# BoardSchematics.net
KiCad netlist of a schematic drawn in EAGLE
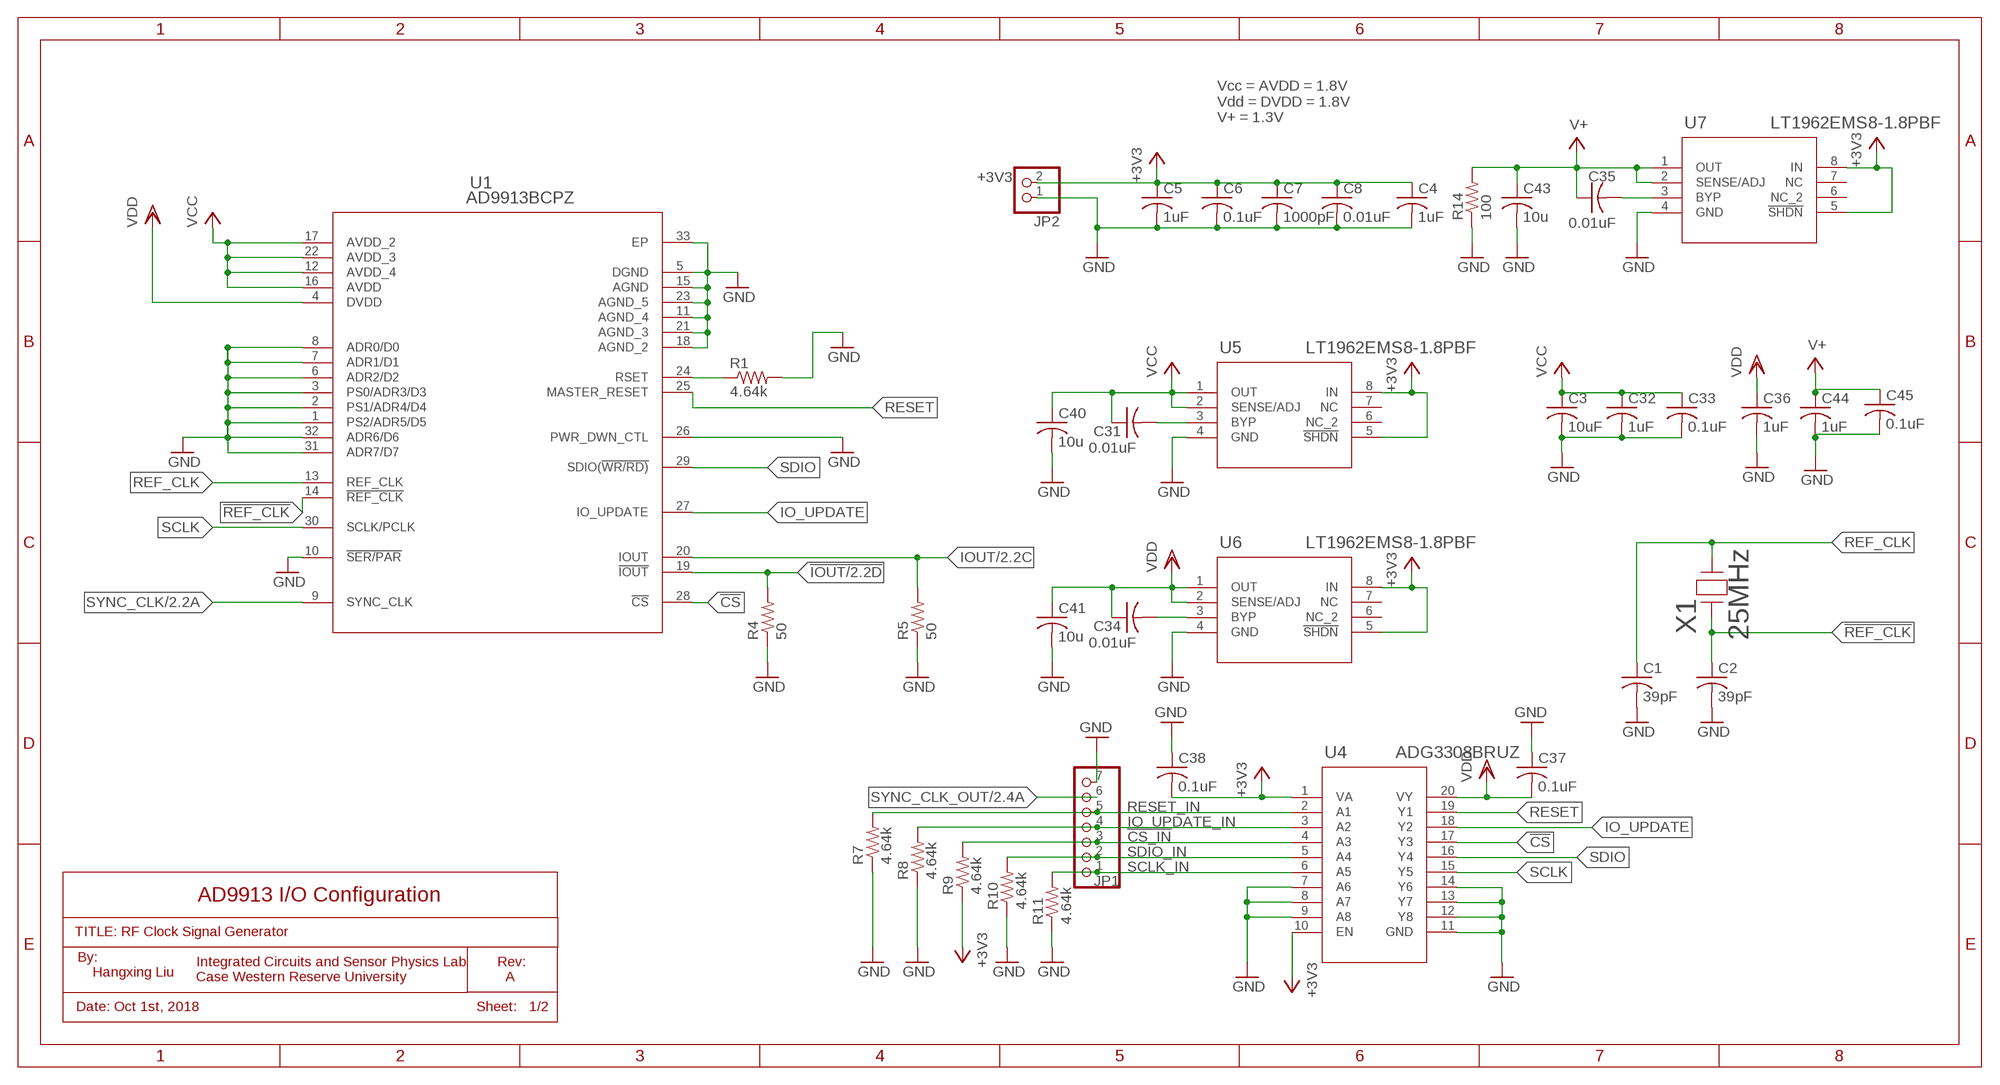
[diagram p0: schematic, sheet 1]
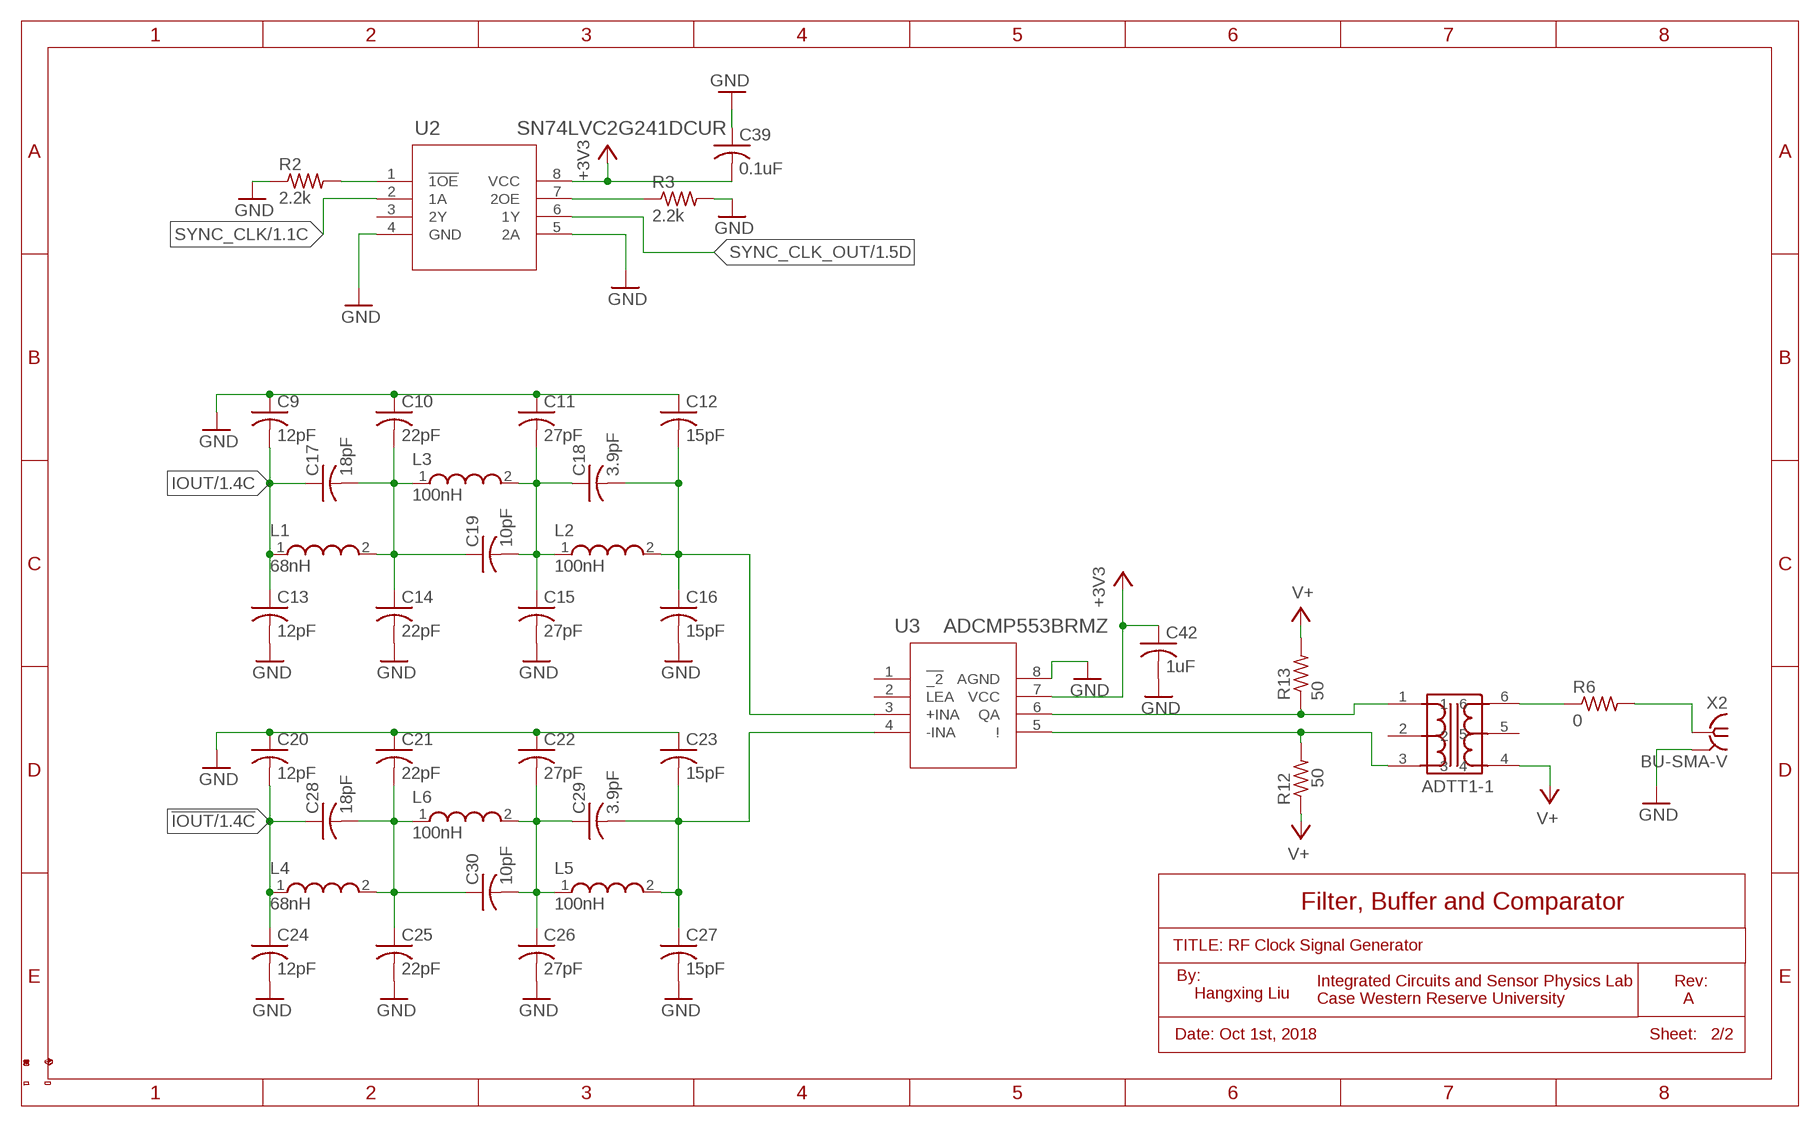
[diagram p1: schematic, sheet 2]

(export (version "E")
  (design (tool "Eeschema 10.0.6"))
  (components
    (comp (ref "ATT1-1")
      (value "PWB-1-CLCD542")
      (footprint "eagle-import:CD542")
      (libsource (lib "eagle-import") (part "PWB-1-CLCD542"))
    )
    (comp (ref "C9")
      (value "12pF")
      (footprint "eagle-import:C0603K")
      (libsource (lib "eagle-import") (part "C-USC0603K"))
    )
    (comp (ref "C10")
      (value "22pF")
      (footprint "eagle-import:C0603K")
      (libsource (lib "eagle-import") (part "C-USC0603K"))
    )
    (comp (ref "C11")
      (value "27pF")
      (footprint "eagle-import:C0603K")
      (libsource (lib "eagle-import") (part "C-USC0603K"))
    )
    (comp (ref "C12")
      (value "15pF")
      (footprint "eagle-import:C0603K")
      (libsource (lib "eagle-import") (part "C-USC0603K"))
    )
    (comp (ref "C13")
      (value "12pF")
      (footprint "eagle-import:C0603K")
      (libsource (lib "eagle-import") (part "C-USC0603K"))
    )
    (comp (ref "C14")
      (value "22pF")
      (footprint "eagle-import:C0603K")
      (libsource (lib "eagle-import") (part "C-USC0603K"))
    )
    (comp (ref "C15")
      (value "27pF")
      (footprint "eagle-import:C0603K")
      (libsource (lib "eagle-import") (part "C-USC0603K"))
    )
    (comp (ref "C16")
      (value "15pF")
      (footprint "eagle-import:C0603K")
      (libsource (lib "eagle-import") (part "C-USC0603K"))
    )
    (comp (ref "C17")
      (value "18pF")
      (footprint "eagle-import:C0603K")
      (libsource (lib "eagle-import") (part "C-USC0603K"))
    )
    (comp (ref "C18")
      (value "3.9pF")
      (footprint "eagle-import:C0603K")
      (libsource (lib "eagle-import") (part "C-USC0603K"))
    )
    (comp (ref "C19")
      (value "10pF")
      (footprint "eagle-import:C0603K")
      (libsource (lib "eagle-import") (part "C-USC0603K"))
    )
    (comp (ref "C20")
      (value "12pF")
      (footprint "eagle-import:C0603K")
      (libsource (lib "eagle-import") (part "C-USC0603K"))
    )
    (comp (ref "C21")
      (value "22pF")
      (footprint "eagle-import:C0603K")
      (libsource (lib "eagle-import") (part "C-USC0603K"))
    )
    (comp (ref "C22")
      (value "27pF")
      (footprint "eagle-import:C0603K")
      (libsource (lib "eagle-import") (part "C-USC0603K"))
    )
    (comp (ref "C23")
      (value "15pF")
      (footprint "eagle-import:C0603K")
      (libsource (lib "eagle-import") (part "C-USC0603K"))
    )
    (comp (ref "C24")
      (value "12pF")
      (footprint "eagle-import:C0603K")
      (libsource (lib "eagle-import") (part "C-USC0603K"))
    )
    (comp (ref "C25")
      (value "22pF")
      (footprint "eagle-import:C0603K")
      (libsource (lib "eagle-import") (part "C-USC0603K"))
    )
    (comp (ref "C26")
      (value "27pF")
      (footprint "eagle-import:C0603K")
      (libsource (lib "eagle-import") (part "C-USC0603K"))
    )
    (comp (ref "C27")
      (value "15pF")
      (footprint "eagle-import:C0603K")
      (libsource (lib "eagle-import") (part "C-USC0603K"))
    )
    (comp (ref "C28")
      (value "18pF")
      (footprint "eagle-import:C0603K")
      (libsource (lib "eagle-import") (part "C-USC0603K"))
    )
    (comp (ref "C29")
      (value "3.9pF")
      (footprint "eagle-import:C0603K")
      (libsource (lib "eagle-import") (part "C-USC0603K"))
    )
    (comp (ref "C30")
      (value "10pF")
      (footprint "eagle-import:C0603K")
      (libsource (lib "eagle-import") (part "C-USC0603K"))
    )
    (comp (ref "C39")
      (value "0.1uF")
      (footprint "eagle-import:C0603K")
      (libsource (lib "eagle-import") (part "C-USC0603K"))
    )
    (comp (ref "C42")
      (value "1uF")
      (footprint "eagle-import:C0603K")
      (libsource (lib "eagle-import") (part "C-USC0603K"))
    )
    (comp (ref "L1")
      (value "68nH")
      (footprint "eagle-import:WE-PMI_1008")
      (libsource (lib "eagle-import") (part "WE-PMI_1008"))
    )
    (comp (ref "L2")
      (value "100nH")
      (footprint "eagle-import:WE-PMI_1008")
      (libsource (lib "eagle-import") (part "WE-PMI_1008"))
    )
    (comp (ref "L3")
      (value "100nH")
      (footprint "eagle-import:WE-PMI_1008")
      (libsource (lib "eagle-import") (part "WE-PMI_1008"))
    )
    (comp (ref "L4")
      (value "68nH")
      (footprint "eagle-import:WE-PMI_1008")
      (libsource (lib "eagle-import") (part "WE-PMI_1008"))
    )
    (comp (ref "L5")
      (value "100nH")
      (footprint "eagle-import:WE-PMI_1008")
      (libsource (lib "eagle-import") (part "WE-PMI_1008"))
    )
    (comp (ref "L6")
      (value "100nH")
      (footprint "eagle-import:WE-PMI_1008")
      (libsource (lib "eagle-import") (part "WE-PMI_1008"))
    )
    (comp (ref "R2")
      (value "2.2k")
      (footprint "eagle-import:R0603")
      (libsource (lib "eagle-import") (part "R-US_R0603"))
    )
    (comp (ref "R3")
      (value "2.2k")
      (footprint "eagle-import:R0603")
      (libsource (lib "eagle-import") (part "R-US_R0603"))
    )
    (comp (ref "R6")
      (value "0")
      (footprint "eagle-import:R0603")
      (libsource (lib "eagle-import") (part "R-US_R0603"))
    )
    (comp (ref "R12")
      (value "50")
      (footprint "eagle-import:R0603")
      (libsource (lib "eagle-import") (part "R-US_R0603"))
    )
    (comp (ref "R13")
      (value "50")
      (footprint "eagle-import:R0603")
      (libsource (lib "eagle-import") (part "R-US_R0603"))
    )
    (comp (ref "U2")
      (value "SN74LVC2G241DCUR")
      (footprint "eagle-import:DCU8")
      (libsource (lib "eagle-import") (part "SN74LVC2G241DCUR"))
    )
    (comp (ref "U3")
      (value "ADCMP553BRMZ")
      (footprint "eagle-import:RM_8")
      (libsource (lib "eagle-import") (part "ADCMP553BRMZ"))
    )
    (comp (ref "X2")
      (value "BU-SMA-V")
      (footprint "eagle-import:BU-SMA-V")
      (libsource (lib "eagle-import") (part "BU-SMA-V"))
    )
    (comp (ref "C1")
      (value "39pF")
      (footprint "eagle-import:C1608")
      (libsource (lib "eagle-import") (part "C-USC1608"))
    )
    (comp (ref "C2")
      (value "39pF")
      (footprint "eagle-import:C1608")
      (libsource (lib "eagle-import") (part "C-USC1608"))
    )
    (comp (ref "C3")
      (value "10uF")
      (footprint "eagle-import:C0603K")
      (libsource (lib "eagle-import") (part "C-USC0603K"))
    )
    (comp (ref "C4")
      (value "1uF")
      (footprint "eagle-import:C0603K")
      (libsource (lib "eagle-import") (part "C-USC0603K"))
    )
    (comp (ref "C5")
      (value "1uF")
      (footprint "eagle-import:C0603K")
      (libsource (lib "eagle-import") (part "C-USC0603K"))
    )
    (comp (ref "C6")
      (value "0.1uF")
      (footprint "eagle-import:C0603K")
      (libsource (lib "eagle-import") (part "C-USC0603K"))
    )
    (comp (ref "C7")
      (value "1000pF")
      (footprint "eagle-import:C0603K")
      (libsource (lib "eagle-import") (part "C-USC0603K"))
    )
    (comp (ref "C8")
      (value "0.01uF")
      (footprint "eagle-import:C0603K")
      (libsource (lib "eagle-import") (part "C-USC0603K"))
    )
    (comp (ref "C31")
      (value "0.01uF")
      (footprint "eagle-import:C0603K")
      (libsource (lib "eagle-import") (part "C-USC0603K"))
    )
    (comp (ref "C32")
      (value "1uF")
      (footprint "eagle-import:C0603K")
      (libsource (lib "eagle-import") (part "C-USC0603K"))
    )
    (comp (ref "C33")
      (value "0.1uF")
      (footprint "eagle-import:C0603K")
      (libsource (lib "eagle-import") (part "C-USC0603K"))
    )
    (comp (ref "C34")
      (value "0.01uF")
      (footprint "eagle-import:C0603K")
      (libsource (lib "eagle-import") (part "C-USC0603K"))
    )
    (comp (ref "C35")
      (value "0.01uF")
      (footprint "eagle-import:C0603K")
      (libsource (lib "eagle-import") (part "C-USC0603K"))
    )
    (comp (ref "C36")
      (value "1uF")
      (footprint "eagle-import:C0603K")
      (libsource (lib "eagle-import") (part "C-USC0603K"))
    )
    (comp (ref "C37")
      (value "0.1uF")
      (footprint "eagle-import:C0603K")
      (libsource (lib "eagle-import") (part "C-USC0603K"))
    )
    (comp (ref "C38")
      (value "0.1uF")
      (footprint "eagle-import:C0603K")
      (libsource (lib "eagle-import") (part "C-USC0603K"))
    )
    (comp (ref "C40")
      (value "10u")
      (footprint "eagle-import:C0603K")
      (libsource (lib "eagle-import") (part "C-USC0603K"))
    )
    (comp (ref "C41")
      (value "10u")
      (footprint "eagle-import:C0603K")
      (libsource (lib "eagle-import") (part "C-USC0603K"))
    )
    (comp (ref "C43")
      (value "10u")
      (footprint "eagle-import:C0603K")
      (libsource (lib "eagle-import") (part "C-USC0603K"))
    )
    (comp (ref "C44")
      (value "1uF")
      (footprint "eagle-import:C0603K")
      (libsource (lib "eagle-import") (part "C-USC0603K"))
    )
    (comp (ref "C45")
      (value "0.1uF")
      (footprint "eagle-import:C0603K")
      (libsource (lib "eagle-import") (part "C-USC0603K"))
    )
    (comp (ref "JP1")
      (value "PINHD-1X7")
      (footprint "eagle-import:1X07")
      (libsource (lib "eagle-import") (part "PINHD-1X7"))
    )
    (comp (ref "JP2")
      (value "PINHD-1X2")
      (footprint "eagle-import:1X02")
      (libsource (lib "eagle-import") (part "PINHD-1X2"))
    )
    (comp (ref "R1")
      (value "4.64k")
      (footprint "eagle-import:R0603")
      (libsource (lib "eagle-import") (part "R-US_R0603"))
    )
    (comp (ref "R4")
      (value "50")
      (footprint "eagle-import:R0603")
      (libsource (lib "eagle-import") (part "R-US_R0603"))
    )
    (comp (ref "R5")
      (value "50")
      (footprint "eagle-import:R0603")
      (libsource (lib "eagle-import") (part "R-US_R0603"))
    )
    (comp (ref "R7")
      (value "4.64k")
      (footprint "eagle-import:R0603")
      (libsource (lib "eagle-import") (part "R-US_R0603"))
    )
    (comp (ref "R8")
      (value "4.64k")
      (footprint "eagle-import:R0603")
      (libsource (lib "eagle-import") (part "R-US_R0603"))
    )
    (comp (ref "R9")
      (value "4.64k")
      (footprint "eagle-import:R0603")
      (libsource (lib "eagle-import") (part "R-US_R0603"))
    )
    (comp (ref "R10")
      (value "4.64k")
      (footprint "eagle-import:R0603")
      (libsource (lib "eagle-import") (part "R-US_R0603"))
    )
    (comp (ref "R11")
      (value "4.64k")
      (footprint "eagle-import:R0603")
      (libsource (lib "eagle-import") (part "R-US_R0603"))
    )
    (comp (ref "R14")
      (value "100")
      (footprint "eagle-import:R0603")
      (libsource (lib "eagle-import") (part "R-US_R0603"))
    )
    (comp (ref "U1")
      (value "AD9913BCPZ")
      (footprint "eagle-import:CP_32_2")
      (libsource (lib "eagle-import") (part "AD9913BCPZ"))
    )
    (comp (ref "U4")
      (value "ADG3308BRUZ")
      (footprint "eagle-import:RU_20")
      (libsource (lib "eagle-import") (part "ADG3308BRUZ"))
    )
    (comp (ref "U5")
      (value "LT1962EMS8-1.8PBF")
      (footprint "eagle-import:MSOP-8_MS")
      (fields (field (name "MANUFACTURER_PART_NUMBER") "LT1962EMS81.8#PBF"))
      (libsource (lib "eagle-import") (part "LT1962EMS8-1.8PBF"))
    )
    (comp (ref "U6")
      (value "LT1962EMS8-1.8PBF")
      (footprint "eagle-import:MSOP-8_MS")
      (fields (field (name "MANUFACTURER_PART_NUMBER") "LT1962EMS81.8#PBF"))
      (libsource (lib "eagle-import") (part "LT1962EMS8-1.8PBF"))
    )
    (comp (ref "U7")
      (value "LT1962EMS8-1.8PBF")
      (footprint "eagle-import:MSOP-8_MS")
      (fields (field (name "MANUFACTURER_PART_NUMBER") "LT1962EMS81.8#PBF"))
      (libsource (lib "eagle-import") (part "LT1962EMS8-1.8PBF"))
    )
    (comp (ref "X1")
      (value "25MHz")
      (footprint "eagle-import:CRYSTAL_HC49SDLF")
      (fields (field (name "MANUFACTURER_PART_NUMBER") "FOXSDLF250F20"))
      (libsource (lib "eagle-import") (part "FOXSDLF/250F-20"))
    )
  )
  (nets
    (net (code "1") (name "+3V3") (class "Default")
      (node (ref "C38") (pin "2") (pinfunction "2_2") (pintype "passive"))
      (node (ref "C39") (pin "2") (pinfunction "2_2") (pintype "passive"))
      (node (ref "C4") (pin "1") (pinfunction "1_1") (pintype "passive"))
      (node (ref "C42") (pin "1") (pinfunction "1_1") (pintype "passive"))
      (node (ref "C5") (pin "1") (pinfunction "1_1") (pintype "passive"))
      (node (ref "C6") (pin "1") (pinfunction "1_1") (pintype "passive"))
      (node (ref "C7") (pin "1") (pinfunction "1_1") (pintype "passive"))
      (node (ref "C8") (pin "1") (pinfunction "1_1") (pintype "passive"))
      (node (ref "JP2") (pin "2") (pinfunction "2_2") (pintype "passive"))
      (node (ref "R9") (pin "1") (pinfunction "1_1") (pintype "passive"))
      (node (ref "U2") (pin "8") (pinfunction "VCC_8") (pintype "power_in"))
      (node (ref "U3") (pin "7") (pinfunction "VCC_7") (pintype "power_in"))
      (node (ref "U4") (pin "1") (pinfunction "VA_1") (pintype "power_in"))
      (node (ref "U4") (pin "10") (pinfunction "EN_10") (pintype "passive"))
      (node (ref "U5") (pin "5") (pinfunction "~{SHDN}_5") (pintype "output"))
      (node (ref "U5") (pin "8") (pinfunction "IN_8") (pintype "input"))
      (node (ref "U6") (pin "5") (pinfunction "~{SHDN}_5") (pintype "output"))
      (node (ref "U6") (pin "8") (pinfunction "IN_8") (pintype "input"))
      (node (ref "U7") (pin "5") (pinfunction "~{SHDN}_5") (pintype "output"))
      (node (ref "U7") (pin "8") (pinfunction "IN_8") (pintype "input"))
    )
    (net (code "2") (name "GND") (class "Default")
      (node (ref "C1") (pin "2") (pinfunction "2_2") (pintype "passive"))
      (node (ref "C10") (pin "1") (pinfunction "1_1") (pintype "passive"))
      (node (ref "C11") (pin "1") (pinfunction "1_1") (pintype "passive"))
      (node (ref "C12") (pin "1") (pinfunction "1_1") (pintype "passive"))
      (node (ref "C13") (pin "2") (pinfunction "2_2") (pintype "passive"))
      (node (ref "C14") (pin "2") (pinfunction "2_2") (pintype "passive"))
      (node (ref "C15") (pin "2") (pinfunction "2_2") (pintype "passive"))
      (node (ref "C16") (pin "2") (pinfunction "2_2") (pintype "passive"))
      (node (ref "C2") (pin "2") (pinfunction "2_2") (pintype "passive"))
      (node (ref "C20") (pin "1") (pinfunction "1_1") (pintype "passive"))
      (node (ref "C21") (pin "1") (pinfunction "1_1") (pintype "passive"))
      (node (ref "C22") (pin "1") (pinfunction "1_1") (pintype "passive"))
      (node (ref "C23") (pin "1") (pinfunction "1_1") (pintype "passive"))
      (node (ref "C24") (pin "2") (pinfunction "2_2") (pintype "passive"))
      (node (ref "C25") (pin "2") (pinfunction "2_2") (pintype "passive"))
      (node (ref "C26") (pin "2") (pinfunction "2_2") (pintype "passive"))
      (node (ref "C27") (pin "2") (pinfunction "2_2") (pintype "passive"))
      (node (ref "C3") (pin "2") (pinfunction "2_2") (pintype "passive"))
      (node (ref "C32") (pin "2") (pinfunction "2_2") (pintype "passive"))
      (node (ref "C33") (pin "2") (pinfunction "2_2") (pintype "passive"))
      (node (ref "C36") (pin "2") (pinfunction "2_2") (pintype "passive"))
      (node (ref "C37") (pin "1") (pinfunction "1_1") (pintype "passive"))
      (node (ref "C38") (pin "1") (pinfunction "1_1") (pintype "passive"))
      (node (ref "C39") (pin "1") (pinfunction "1_1") (pintype "passive"))
      (node (ref "C4") (pin "2") (pinfunction "2_2") (pintype "passive"))
      (node (ref "C40") (pin "2") (pinfunction "2_2") (pintype "passive"))
      (node (ref "C41") (pin "2") (pinfunction "2_2") (pintype "passive"))
      (node (ref "C42") (pin "2") (pinfunction "2_2") (pintype "passive"))
      (node (ref "C43") (pin "2") (pinfunction "2_2") (pintype "passive"))
      (node (ref "C44") (pin "2") (pinfunction "2_2") (pintype "passive"))
      (node (ref "C45") (pin "2") (pinfunction "2_2") (pintype "passive"))
      (node (ref "C5") (pin "2") (pinfunction "2_2") (pintype "passive"))
      (node (ref "C6") (pin "2") (pinfunction "2_2") (pintype "passive"))
      (node (ref "C7") (pin "2") (pinfunction "2_2") (pintype "passive"))
      (node (ref "C8") (pin "2") (pinfunction "2_2") (pintype "passive"))
      (node (ref "C9") (pin "1") (pinfunction "1_1") (pintype "passive"))
      (node (ref "JP1") (pin "7") (pinfunction "7_7") (pintype "passive"))
      (node (ref "JP2") (pin "1") (pinfunction "1_1") (pintype "passive"))
      (node (ref "R1") (pin "2") (pinfunction "2_2") (pintype "passive"))
      (node (ref "R10") (pin "1") (pinfunction "1_1") (pintype "passive"))
      (node (ref "R11") (pin "1") (pinfunction "1_1") (pintype "passive"))
      (node (ref "R14") (pin "1") (pinfunction "1_1") (pintype "passive"))
      (node (ref "R2") (pin "1") (pinfunction "1_1") (pintype "passive"))
      (node (ref "R3") (pin "2") (pinfunction "2_2") (pintype "passive"))
      (node (ref "R4") (pin "1") (pinfunction "1_1") (pintype "passive"))
      (node (ref "R5") (pin "1") (pinfunction "1_1") (pintype "passive"))
      (node (ref "R7") (pin "1") (pinfunction "1_1") (pintype "passive"))
      (node (ref "R8") (pin "1") (pinfunction "1_1") (pintype "passive"))
      (node (ref "U1") (pin "1") (pinfunction "PS2/ADR5/D5_1") (pintype "passive"))
      (node (ref "U1") (pin "10") (pinfunction "~{SER/PAR}_10") (pintype "passive"))
      (node (ref "U1") (pin "11") (pinfunction "AGND_4_11") (pintype "passive"))
      (node (ref "U1") (pin "15") (pinfunction "AGND_15") (pintype "passive"))
      (node (ref "U1") (pin "18") (pinfunction "AGND_2_18") (pintype "passive"))
      (node (ref "U1") (pin "2") (pinfunction "PS1/ADR4/D4_2") (pintype "passive"))
      (node (ref "U1") (pin "21") (pinfunction "AGND_3_21") (pintype "passive"))
      (node (ref "U1") (pin "23") (pinfunction "AGND_5_23") (pintype "passive"))
      (node (ref "U1") (pin "26") (pinfunction "PWR_DWN_CTL_26") (pintype "passive"))
      (node (ref "U1") (pin "3") (pinfunction "PS0/ADR3/D3_3") (pintype "passive"))
      (node (ref "U1") (pin "31") (pinfunction "ADR7/D7_31") (pintype "passive"))
      (node (ref "U1") (pin "32") (pinfunction "ADR6/D6_32") (pintype "passive"))
      (node (ref "U1") (pin "33") (pinfunction "EP_33") (pintype "passive"))
      (node (ref "U1") (pin "5") (pinfunction "DGND_5") (pintype "passive"))
      (node (ref "U1") (pin "6") (pinfunction "ADR2/D2_6") (pintype "passive"))
      (node (ref "U1") (pin "7") (pinfunction "ADR1/D1_7") (pintype "passive"))
      (node (ref "U1") (pin "8") (pinfunction "ADR0/D0_8") (pintype "passive"))
      (node (ref "U2") (pin "4") (pinfunction "GND_4") (pintype "power_in"))
      (node (ref "U2") (pin "5") (pinfunction "2A_5") (pintype "input"))
      (node (ref "U3") (pin "8") (pinfunction "AGND_8") (pintype "passive"))
      (node (ref "U4") (pin "11") (pinfunction "GND_11") (pintype "passive"))
      (node (ref "U4") (pin "12") (pinfunction "Y8_12") (pintype "passive"))
      (node (ref "U4") (pin "13") (pinfunction "Y7_13") (pintype "passive"))
      (node (ref "U4") (pin "14") (pinfunction "Y6_14") (pintype "passive"))
      (node (ref "U4") (pin "7") (pinfunction "A6_7") (pintype "passive"))
      (node (ref "U4") (pin "8") (pinfunction "A7_8") (pintype "passive"))
      (node (ref "U4") (pin "9") (pinfunction "A8_9") (pintype "passive"))
      (node (ref "U5") (pin "4") (pinfunction "GND_4") (pintype "power_in"))
      (node (ref "U6") (pin "4") (pinfunction "GND_4") (pintype "power_in"))
      (node (ref "U7") (pin "4") (pinfunction "GND_4") (pintype "power_in"))
      (node (ref "X2") (pin "2") (pinfunction "2_2") (pintype "passive"))
      (node (ref "X2") (pin "3") (pinfunction "2_3") (pintype "passive"))
      (node (ref "X2") (pin "4") (pinfunction "2_4") (pintype "passive"))
      (node (ref "X2") (pin "5") (pinfunction "2_5") (pintype "passive"))
    )
    (net (code "3") (name "IOUT") (class "Default")
      (node (ref "C13") (pin "1") (pinfunction "1_1") (pintype "passive"))
      (node (ref "C17") (pin "1") (pinfunction "1_1") (pintype "passive"))
      (node (ref "C9") (pin "2") (pinfunction "2_2") (pintype "passive"))
      (node (ref "L1") (pin "1") (pinfunction "1_1") (pintype "passive"))
      (node (ref "R5") (pin "2") (pinfunction "2_2") (pintype "passive"))
      (node (ref "U1") (pin "20") (pinfunction "IOUT_20") (pintype "passive"))
    )
    (net (code "4") (name "IO_UPDATE") (class "Default")
      (node (ref "U1") (pin "27") (pinfunction "IO_UPDATE_27") (pintype "passive"))
      (node (ref "U4") (pin "18") (pinfunction "Y2_18") (pintype "passive"))
    )
    (net (code "5") (name "IO_UPDATE_IN") (class "Default")
      (node (ref "JP1") (pin "4") (pinfunction "4_4") (pintype "passive"))
      (node (ref "R8") (pin "2") (pinfunction "2_2") (pintype "passive"))
      (node (ref "U4") (pin "3") (pinfunction "A2_3") (pintype "passive"))
    )
    (net (code "6") (name "Net-(ATT1-1-Pad6)") (class "Default")
      (node (ref "ATT1-1") (pin "6") (pinfunction "6_6") (pintype "bidirectional"))
      (node (ref "R6") (pin "1") (pinfunction "1_1") (pintype "passive"))
    )
    (net (code "7") (name "Net-(C10-Pad2)") (class "Default")
      (node (ref "C10") (pin "2") (pinfunction "2_2") (pintype "passive"))
      (node (ref "C14") (pin "1") (pinfunction "1_1") (pintype "passive"))
      (node (ref "C17") (pin "2") (pinfunction "2_2") (pintype "passive"))
      (node (ref "C19") (pin "1") (pinfunction "1_1") (pintype "passive"))
      (node (ref "L1") (pin "2") (pinfunction "2_2") (pintype "passive"))
      (node (ref "L3") (pin "1") (pinfunction "1_1") (pintype "passive"))
    )
    (net (code "8") (name "Net-(C11-Pad2)") (class "Default")
      (node (ref "C11") (pin "2") (pinfunction "2_2") (pintype "passive"))
      (node (ref "C15") (pin "1") (pinfunction "1_1") (pintype "passive"))
      (node (ref "C18") (pin "1") (pinfunction "1_1") (pintype "passive"))
      (node (ref "C19") (pin "2") (pinfunction "2_2") (pintype "passive"))
      (node (ref "L2") (pin "1") (pinfunction "1_1") (pintype "passive"))
      (node (ref "L3") (pin "2") (pinfunction "2_2") (pintype "passive"))
    )
    (net (code "9") (name "Net-(C21-Pad2)") (class "Default")
      (node (ref "C21") (pin "2") (pinfunction "2_2") (pintype "passive"))
      (node (ref "C25") (pin "1") (pinfunction "1_1") (pintype "passive"))
      (node (ref "C28") (pin "2") (pinfunction "2_2") (pintype "passive"))
      (node (ref "C30") (pin "1") (pinfunction "1_1") (pintype "passive"))
      (node (ref "L4") (pin "2") (pinfunction "2_2") (pintype "passive"))
      (node (ref "L6") (pin "1") (pinfunction "1_1") (pintype "passive"))
    )
    (net (code "10") (name "Net-(C22-Pad2)") (class "Default")
      (node (ref "C22") (pin "2") (pinfunction "2_2") (pintype "passive"))
      (node (ref "C26") (pin "1") (pinfunction "1_1") (pintype "passive"))
      (node (ref "C29") (pin "1") (pinfunction "1_1") (pintype "passive"))
      (node (ref "C30") (pin "2") (pinfunction "2_2") (pintype "passive"))
      (node (ref "L5") (pin "1") (pinfunction "1_1") (pintype "passive"))
      (node (ref "L6") (pin "2") (pinfunction "2_2") (pintype "passive"))
    )
    (net (code "11") (name "Net-(R6-Pad2)") (class "Default")
      (node (ref "R6") (pin "2") (pinfunction "2_2") (pintype "passive"))
      (node (ref "X2") (pin "1") (pinfunction "1_1") (pintype "passive"))
    )
    (net (code "12") (name "Net-(U1-RSET)") (class "Default")
      (node (ref "R1") (pin "1") (pinfunction "1_1") (pintype "passive"))
      (node (ref "U1") (pin "24") (pinfunction "RSET_24") (pintype "passive"))
    )
    (net (code "13") (name "Net-(U2-2OE)") (class "Default")
      (node (ref "R3") (pin "1") (pinfunction "1_1") (pintype "passive"))
      (node (ref "U2") (pin "7") (pinfunction "2OE_7") (pintype "input"))
    )
    (net (code "14") (name "Net-(U2-~{1OE})") (class "Default")
      (node (ref "R2") (pin "2") (pinfunction "2_2") (pintype "passive"))
      (node (ref "U2") (pin "1") (pinfunction "~{1OE}_1") (pintype "input"))
    )
    (net (code "15") (name "Net-(U3-+INA)") (class "Default")
      (node (ref "C12") (pin "2") (pinfunction "2_2") (pintype "passive"))
      (node (ref "C16") (pin "1") (pinfunction "1_1") (pintype "passive"))
      (node (ref "C18") (pin "2") (pinfunction "2_2") (pintype "passive"))
      (node (ref "L2") (pin "2") (pinfunction "2_2") (pintype "passive"))
      (node (ref "U3") (pin "3") (pinfunction "+INA_3") (pintype "passive"))
    )
    (net (code "16") (name "Net-(U3--INA)") (class "Default")
      (node (ref "C23") (pin "2") (pinfunction "2_2") (pintype "passive"))
      (node (ref "C27") (pin "1") (pinfunction "1_1") (pintype "passive"))
      (node (ref "C29") (pin "2") (pinfunction "2_2") (pintype "passive"))
      (node (ref "L5") (pin "2") (pinfunction "2_2") (pintype "passive"))
      (node (ref "U3") (pin "4") (pinfunction "-INA_4") (pintype "passive"))
    )
    (net (code "17") (name "Net-(U3-QA)") (class "Default")
      (node (ref "ATT1-1") (pin "1") (pinfunction "1_1") (pintype "bidirectional"))
      (node (ref "R13") (pin "1") (pinfunction "1_1") (pintype "passive"))
      (node (ref "U3") (pin "6") (pinfunction "QA_6") (pintype "passive"))
    )
    (net (code "18") (name "Net-(U3-~)") (class "Default")
      (node (ref "ATT1-1") (pin "3") (pinfunction "3_3") (pintype "bidirectional"))
      (node (ref "R12") (pin "2") (pinfunction "2_2") (pintype "passive"))
      (node (ref "U3") (pin "5") (pinfunction "~_5") (pintype "passive"))
    )
    (net (code "19") (name "Net-(U5-BYP)") (class "Default")
      (node (ref "C31") (pin "2") (pinfunction "2_2") (pintype "passive"))
      (node (ref "U5") (pin "3") (pinfunction "BYP_3") (pintype "passive"))
    )
    (net (code "20") (name "Net-(U6-BYP)") (class "Default")
      (node (ref "C34") (pin "2") (pinfunction "2_2") (pintype "passive"))
      (node (ref "U6") (pin "3") (pinfunction "BYP_3") (pintype "passive"))
    )
    (net (code "21") (name "Net-(U7-BYP)") (class "Default")
      (node (ref "C35") (pin "2") (pinfunction "2_2") (pintype "passive"))
      (node (ref "U7") (pin "3") (pinfunction "BYP_3") (pintype "passive"))
    )
    (net (code "22") (name "REF_CLK") (class "Default")
      (node (ref "C1") (pin "1") (pinfunction "1_1") (pintype "passive"))
      (node (ref "U1") (pin "13") (pinfunction "REF_CLK_13") (pintype "passive"))
      (node (ref "X1") (pin "2") (pinfunction "2_2") (pintype "passive"))
    )
    (net (code "23") (name "RESET") (class "Default")
      (node (ref "U1") (pin "25") (pinfunction "MASTER_RESET_25") (pintype "passive"))
      (node (ref "U4") (pin "19") (pinfunction "Y1_19") (pintype "passive"))
    )
    (net (code "24") (name "RESET_IN") (class "Default")
      (node (ref "JP1") (pin "5") (pinfunction "5_5") (pintype "passive"))
      (node (ref "R7") (pin "2") (pinfunction "2_2") (pintype "passive"))
      (node (ref "U4") (pin "2") (pinfunction "A1_2") (pintype "passive"))
    )
    (net (code "25") (name "SCLK") (class "Default")
      (node (ref "U1") (pin "30") (pinfunction "SCLK/PCLK_30") (pintype "passive"))
      (node (ref "U4") (pin "15") (pinfunction "Y5_15") (pintype "passive"))
    )
    (net (code "26") (name "SCLK_IN") (class "Default")
      (node (ref "JP1") (pin "1") (pinfunction "1_1") (pintype "passive"))
      (node (ref "R11") (pin "2") (pinfunction "2_2") (pintype "passive"))
      (node (ref "U4") (pin "6") (pinfunction "A5_6") (pintype "passive"))
    )
    (net (code "27") (name "SDIO") (class "Default")
      (node (ref "U1") (pin "29") (pinfunction "SDIO(~{WR/RD})_29") (pintype "passive"))
      (node (ref "U4") (pin "16") (pinfunction "Y4_16") (pintype "passive"))
    )
    (net (code "28") (name "SDIO_IN") (class "Default")
      (node (ref "JP1") (pin "2") (pinfunction "2_2") (pintype "passive"))
      (node (ref "R10") (pin "2") (pinfunction "2_2") (pintype "passive"))
      (node (ref "U4") (pin "5") (pinfunction "A4_5") (pintype "passive"))
    )
    (net (code "29") (name "SYNC_CLK") (class "Default")
      (node (ref "U1") (pin "9") (pinfunction "SYNC_CLK_9") (pintype "passive"))
      (node (ref "U2") (pin "2") (pinfunction "1A_2") (pintype "input"))
    )
    (net (code "30") (name "SYNC_CLK_OUT") (class "Default")
      (node (ref "JP1") (pin "6") (pinfunction "6_6") (pintype "passive"))
      (node (ref "U2") (pin "6") (pinfunction "1Y_6") (pintype "output"))
    )
    (net (code "31") (name "V+") (class "Default")
      (node (ref "ATT1-1") (pin "4") (pinfunction "4_4") (pintype "bidirectional"))
      (node (ref "C35") (pin "1") (pinfunction "1_1") (pintype "passive"))
      (node (ref "C43") (pin "1") (pinfunction "1_1") (pintype "passive"))
      (node (ref "C44") (pin "1") (pinfunction "1_1") (pintype "passive"))
      (node (ref "C45") (pin "1") (pinfunction "1_1") (pintype "passive"))
      (node (ref "R12") (pin "1") (pinfunction "1_1") (pintype "passive"))
      (node (ref "R13") (pin "2") (pinfunction "2_2") (pintype "passive"))
      (node (ref "R14") (pin "2") (pinfunction "2_2") (pintype "passive"))
      (node (ref "U7") (pin "1") (pinfunction "OUT_1") (pintype "output"))
      (node (ref "U7") (pin "2") (pinfunction "SENSE/ADJ_2") (pintype "input"))
    )
    (net (code "32") (name "VCC") (class "Default")
      (node (ref "C3") (pin "1") (pinfunction "1_1") (pintype "passive"))
      (node (ref "C31") (pin "1") (pinfunction "1_1") (pintype "passive"))
      (node (ref "C32") (pin "1") (pinfunction "1_1") (pintype "passive"))
      (node (ref "C33") (pin "1") (pinfunction "1_1") (pintype "passive"))
      (node (ref "C40") (pin "1") (pinfunction "1_1") (pintype "passive"))
      (node (ref "U1") (pin "12") (pinfunction "AVDD_4_12") (pintype "passive"))
      (node (ref "U1") (pin "16") (pinfunction "AVDD_16") (pintype "passive"))
      (node (ref "U1") (pin "17") (pinfunction "AVDD_2_17") (pintype "passive"))
      (node (ref "U1") (pin "22") (pinfunction "AVDD_3_22") (pintype "passive"))
      (node (ref "U5") (pin "1") (pinfunction "OUT_1") (pintype "output"))
      (node (ref "U5") (pin "2") (pinfunction "SENSE/ADJ_2") (pintype "input"))
    )
    (net (code "33") (name "VDD") (class "Default")
      (node (ref "C34") (pin "1") (pinfunction "1_1") (pintype "passive"))
      (node (ref "C36") (pin "1") (pinfunction "1_1") (pintype "passive"))
      (node (ref "C37") (pin "2") (pinfunction "2_2") (pintype "passive"))
      (node (ref "C41") (pin "1") (pinfunction "1_1") (pintype "passive"))
      (node (ref "U1") (pin "4") (pinfunction "DVDD_4") (pintype "passive"))
      (node (ref "U4") (pin "20") (pinfunction "VY_20") (pintype "power_in"))
      (node (ref "U6") (pin "1") (pinfunction "OUT_1") (pintype "output"))
      (node (ref "U6") (pin "2") (pinfunction "SENSE/ADJ_2") (pintype "input"))
    )
    (net (code "34") (name "unconnected-(ATT1-1-Pad2)") (class "Default")
      (node (ref "ATT1-1") (pin "2") (pinfunction "2_2") (pintype "bidirectional"))
    )
    (net (code "35") (name "unconnected-(ATT1-1-Pad5)") (class "Default")
      (node (ref "ATT1-1") (pin "5") (pinfunction "5_5") (pintype "bidirectional"))
    )
    (net (code "36") (name "unconnected-(U2-2Y-Pad3)") (class "Default")
      (node (ref "U2") (pin "3") (pinfunction "2Y_3") (pintype "output"))
    )
    (net (code "37") (name "unconnected-(U3-LEA-Pad2)") (class "Default")
      (node (ref "U3") (pin "2") (pinfunction "LEA_2") (pintype "passive"))
    )
    (net (code "38") (name "unconnected-(U3-~{_2}-Pad1)") (class "Default")
      (node (ref "U3") (pin "1") (pinfunction "~{_2}_1") (pintype "passive"))
    )
    (net (code "39") (name "unconnected-(U5-NC-Pad7)") (class "Default")
      (node (ref "U5") (pin "7") (pinfunction "NC_7") (pintype "no_connect"))
    )
    (net (code "40") (name "unconnected-(U5-NC_2-Pad6)") (class "Default")
      (node (ref "U5") (pin "6") (pinfunction "NC_2_6") (pintype "no_connect"))
    )
    (net (code "41") (name "unconnected-(U6-NC-Pad7)") (class "Default")
      (node (ref "U6") (pin "7") (pinfunction "NC_7") (pintype "no_connect"))
    )
    (net (code "42") (name "unconnected-(U6-NC_2-Pad6)") (class "Default")
      (node (ref "U6") (pin "6") (pinfunction "NC_2_6") (pintype "no_connect"))
    )
    (net (code "43") (name "unconnected-(U7-NC-Pad7)") (class "Default")
      (node (ref "U7") (pin "7") (pinfunction "NC_7") (pintype "no_connect"))
    )
    (net (code "44") (name "unconnected-(U7-NC_2-Pad6)") (class "Default")
      (node (ref "U7") (pin "6") (pinfunction "NC_2_6") (pintype "no_connect"))
    )
    (net (code "45") (name "~{CS_IN}") (class "Default")
      (node (ref "JP1") (pin "3") (pinfunction "3_3") (pintype "passive"))
      (node (ref "R9") (pin "2") (pinfunction "2_2") (pintype "passive"))
      (node (ref "U4") (pin "4") (pinfunction "A3_4") (pintype "passive"))
    )
    (net (code "46") (name "~{CS}") (class "Default")
      (node (ref "U1") (pin "28") (pinfunction "~{CS}_28") (pintype "passive"))
      (node (ref "U4") (pin "17") (pinfunction "Y3_17") (pintype "passive"))
    )
    (net (code "47") (name "~{IOUT}") (class "Default")
      (node (ref "C20") (pin "2") (pinfunction "2_2") (pintype "passive"))
      (node (ref "C24") (pin "1") (pinfunction "1_1") (pintype "passive"))
      (node (ref "C28") (pin "1") (pinfunction "1_1") (pintype "passive"))
      (node (ref "L4") (pin "1") (pinfunction "1_1") (pintype "passive"))
      (node (ref "R4") (pin "2") (pinfunction "2_2") (pintype "passive"))
      (node (ref "U1") (pin "19") (pinfunction "~{IOUT}_19") (pintype "passive"))
    )
    (net (code "48") (name "~{REF_CLK}") (class "Default")
      (node (ref "C2") (pin "1") (pinfunction "1_1") (pintype "passive"))
      (node (ref "U1") (pin "14") (pinfunction "~{REF_CLK}_14") (pintype "passive"))
      (node (ref "X1") (pin "1") (pinfunction "1_1") (pintype "passive"))
    )
  )
)
